# Sheet1.net
KiCad netlist of a schematic drawn in Altium Designer
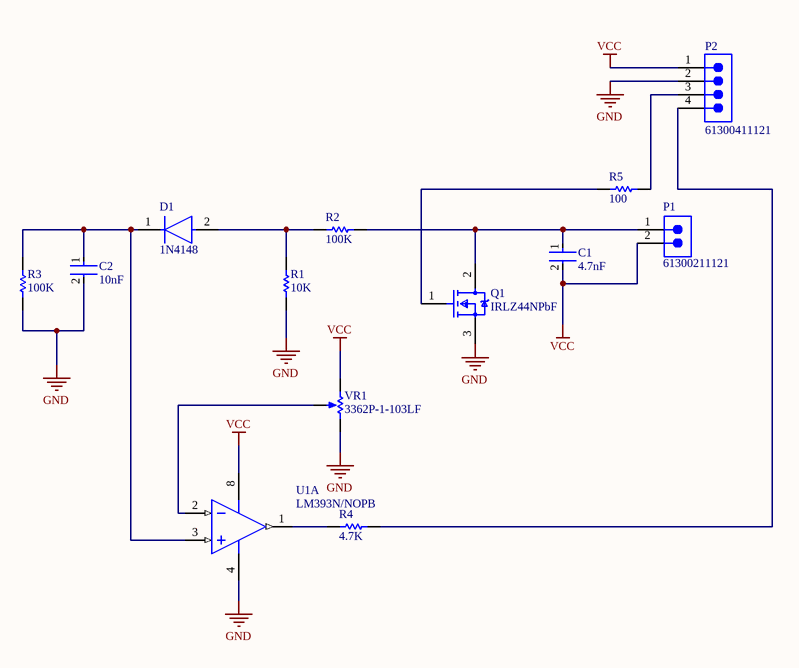
[diagram p0: Sheet1.SchDoc]

(export (version "E")
  (design (tool "Eeschema 10.0.6"))
  (components
    (comp (ref "C1")
      (value "4.7nF")
      (footprint "FP-C320C-MFG")
      (description "CAP CER 0.1UF 50V X7R RADIAL")
      (fields (field (name "TOLERANCE") "5%") (field (name "MANUFACTURER PART NUMBER") "C320C104J5R5TA7301"))
      (libsource (lib "Altium Content Vault") (part "11868f565c42a9108669ba33697ecf6"))
    )
    (comp (ref "C2")
      (value "10nF")
      (footprint "FP-C320C-MFG")
      (description "CAP CER 0.1UF 50V X7R RADIAL")
      (fields (field (name "TOLERANCE") "5%") (field (name "MANUFACTURER PART NUMBER") "C320C104J5R5TA7301"))
      (libsource (lib "Altium Content Vault") (part "11868f565c42a9108669ba33697ecf6"))
    )
    (comp (ref "D1")
      (value "1N4148")
      (footprint "FP-017AG-MFG")
      (description "DIODE GEN PURP 100V 200MA DO35")
      (fields (field (name "VOLTAGE") "100V"))
      (libsource (lib "Altium Content Vault") (part "d7152d700b627762746794eb795d46e"))
    )
    (comp (ref "P1")
      (value "61300211121")
      (footprint "61300211121")
      (description "THT Vertical Pin Header WR-PHD, Pitch 2.54 mm, Single Row, 2 pins")
      (libsource (lib "Altium Content Vault") (part "Header_Male_1R_02P"))
    )
    (comp (ref "P2")
      (value "61300411121")
      (footprint "61300411121")
      (description "THT Vertical Pin Header WR-PHD, Pitch 2.54 mm, Single Row, 4 pins")
      (libsource (lib "Altium Content Vault") (part "Header_Male_1R_04P"))
    )
    (comp (ref "Q1")
      (value "IRLZ44NPbF")
      (footprint "FP-PG-TO220-3-MFG")
      (description "MOSFET N-CH 55V 47A TO220AB")
      (libsource (lib "Altium Content Vault") (part "b09f7f152735e370c1ea22a33fa83d6"))
    )
    (comp (ref "R1")
      (value "10K")
      (footprint "RESA60-630X240")
      (description "Axial Resistor, 100 KOhm, +/- 1%, 0.25 W, -55 to 155 degC, 2-Pin THD, RoHS, Bulk")
      (fields (field (name "TOLERANCE") "1%"))
      (libsource (lib "Altium Content Vault") (part "RES-2"))
    )
    (comp (ref "R2")
      (value "100K")
      (footprint "RESA60-630X240")
      (description "Axial Resistor, 100 KOhm, +/- 1%, 0.25 W, -55 to 155 degC, 2-Pin THD, RoHS, Bulk")
      (fields (field (name "TOLERANCE") "1%"))
      (libsource (lib "Altium Content Vault") (part "RES-2"))
    )
    (comp (ref "R3")
      (value "100K")
      (footprint "RESA60-630X240")
      (description "Axial Resistor, 100 KOhm, +/- 1%, 0.25 W, -55 to 155 degC, 2-Pin THD, RoHS, Bulk")
      (fields (field (name "TOLERANCE") "1%"))
      (libsource (lib "Altium Content Vault") (part "RES-2"))
    )
    (comp (ref "R4")
      (value "4.7K")
      (footprint "RESA60-630X240")
      (description "Axial Resistor, 100 KOhm, +/- 1%, 0.25 W, -55 to 155 degC, 2-Pin THD, RoHS, Bulk")
      (fields (field (name "TOLERANCE") "1%"))
      (libsource (lib "Altium Content Vault") (part "RES-2"))
    )
    (comp (ref "R5")
      (value "100")
      (footprint "RESA60-630X240")
      (description "Axial Resistor, 100 KOhm, +/- 1%, 0.25 W, -55 to 155 degC, 2-Pin THD, RoHS, Bulk")
      (fields (field (name "TOLERANCE") "1%"))
      (libsource (lib "Altium Content Vault") (part "RES-2"))
    )
    (comp (ref "U1")
      (value "LM393N/NOPB")
      (footprint "P0008A")
      (description "Low Power Low Offset Voltage Dual Comparator, 8-pin MDIP, Pb-Free")
      (fields (field (name "MANUFACTURER") "Texas Instruments"))
      (libsource (lib "Altium Content Vault") (part "AN-COMP-LM193-8"))
    )
    (comp (ref "VR1")
      (value "3362P-1-103LF")
      (footprint "BOUR-3362P")
      (description "Square Trimpot(R) Trimming Potentiometer, 10 KOhm, 300 V, -55 to 125 degC, 3-Pin THD, RoHS, Tube")
      (fields (field (name "TOLERANCE") "1%"))
      (libsource (lib "Altium Content Vault") (part "RES-POT-3"))
    )
  )
  (nets
    (net (code "1") (name "GND") (class "Default")
      (node (ref "C2") (pin "2") (pinfunction "2_2") (pintype "passive"))
      (node (ref "P2") (pin "2") (pinfunction "2_2") (pintype "passive"))
      (node (ref "Q1") (pin "3") (pinfunction "S_3") (pintype "passive"))
      (node (ref "R1") (pin "1") (pinfunction "1_1") (pintype "passive"))
      (node (ref "R3") (pin "1") (pinfunction "1_1") (pintype "passive"))
      (node (ref "U1") (pin "4") (pinfunction "GND_4") (pintype "power_in"))
      (node (ref "VR1") (pin "3") (pinfunction "CW_3") (pintype "passive"))
    )
    (net (code "2") (name "Net-(D1-A)") (class "Default")
      (node (ref "D1") (pin "2") (pinfunction "A_2") (pintype "passive"))
      (node (ref "R1") (pin "2") (pinfunction "2_2") (pintype "passive"))
      (node (ref "R2") (pin "1") (pinfunction "1_1") (pintype "passive"))
    )
    (net (code "3") (name "Net-(D1-C)") (class "Default")
      (node (ref "C2") (pin "1") (pinfunction "1_1") (pintype "passive"))
      (node (ref "D1") (pin "1") (pinfunction "C_1") (pintype "passive"))
      (node (ref "R3") (pin "2") (pinfunction "2_2") (pintype "passive"))
      (node (ref "U1") (pin "3") (pinfunction "INA+_3") (pintype "input"))
    )
    (net (code "4") (name "Net-(P2-Pad3)") (class "Default")
      (node (ref "P2") (pin "3") (pinfunction "3_3") (pintype "passive"))
      (node (ref "R5") (pin "2") (pinfunction "2_2") (pintype "passive"))
    )
    (net (code "5") (name "Net-(P2-Pad4)") (class "Default")
      (node (ref "P2") (pin "4") (pinfunction "4_4") (pintype "passive"))
      (node (ref "R4") (pin "2") (pinfunction "2_2") (pintype "passive"))
    )
    (net (code "6") (name "Net-(Q1-D)") (class "Default")
      (node (ref "C1") (pin "1") (pinfunction "1_1") (pintype "passive"))
      (node (ref "P1") (pin "1") (pinfunction "1_1") (pintype "passive"))
      (node (ref "Q1") (pin "2") (pinfunction "D_2") (pintype "passive"))
      (node (ref "R2") (pin "2") (pinfunction "2_2") (pintype "passive"))
    )
    (net (code "7") (name "Net-(Q1-G)") (class "Default")
      (node (ref "Q1") (pin "1") (pinfunction "G_1") (pintype "passive"))
      (node (ref "R5") (pin "1") (pinfunction "1_1") (pintype "passive"))
    )
    (net (code "8") (name "Net-(U1A-INA-)") (class "Default")
      (node (ref "U1") (pin "2") (pinfunction "INA-_2") (pintype "input"))
      (node (ref "VR1") (pin "2") (pinfunction "S_2") (pintype "passive"))
    )
    (net (code "9") (name "Net-(U1A-OUTA)") (class "Default")
      (node (ref "R4") (pin "1") (pinfunction "1_1") (pintype "passive"))
      (node (ref "U1") (pin "1") (pinfunction "OUTA_1") (pintype "output"))
    )
    (net (code "10") (name "VCC") (class "Default")
      (node (ref "C1") (pin "2") (pinfunction "2_2") (pintype "passive"))
      (node (ref "P1") (pin "2") (pinfunction "2_2") (pintype "passive"))
      (node (ref "P2") (pin "1") (pinfunction "1_1") (pintype "passive"))
      (node (ref "U1") (pin "8") (pinfunction "V+_8") (pintype "power_in"))
      (node (ref "VR1") (pin "1") (pinfunction "CCW_1") (pintype "passive"))
    )
  )
)
